# 01072016wearable_v1_3_-_OK.net
KiCad netlist of a schematic drawn in EAGLE
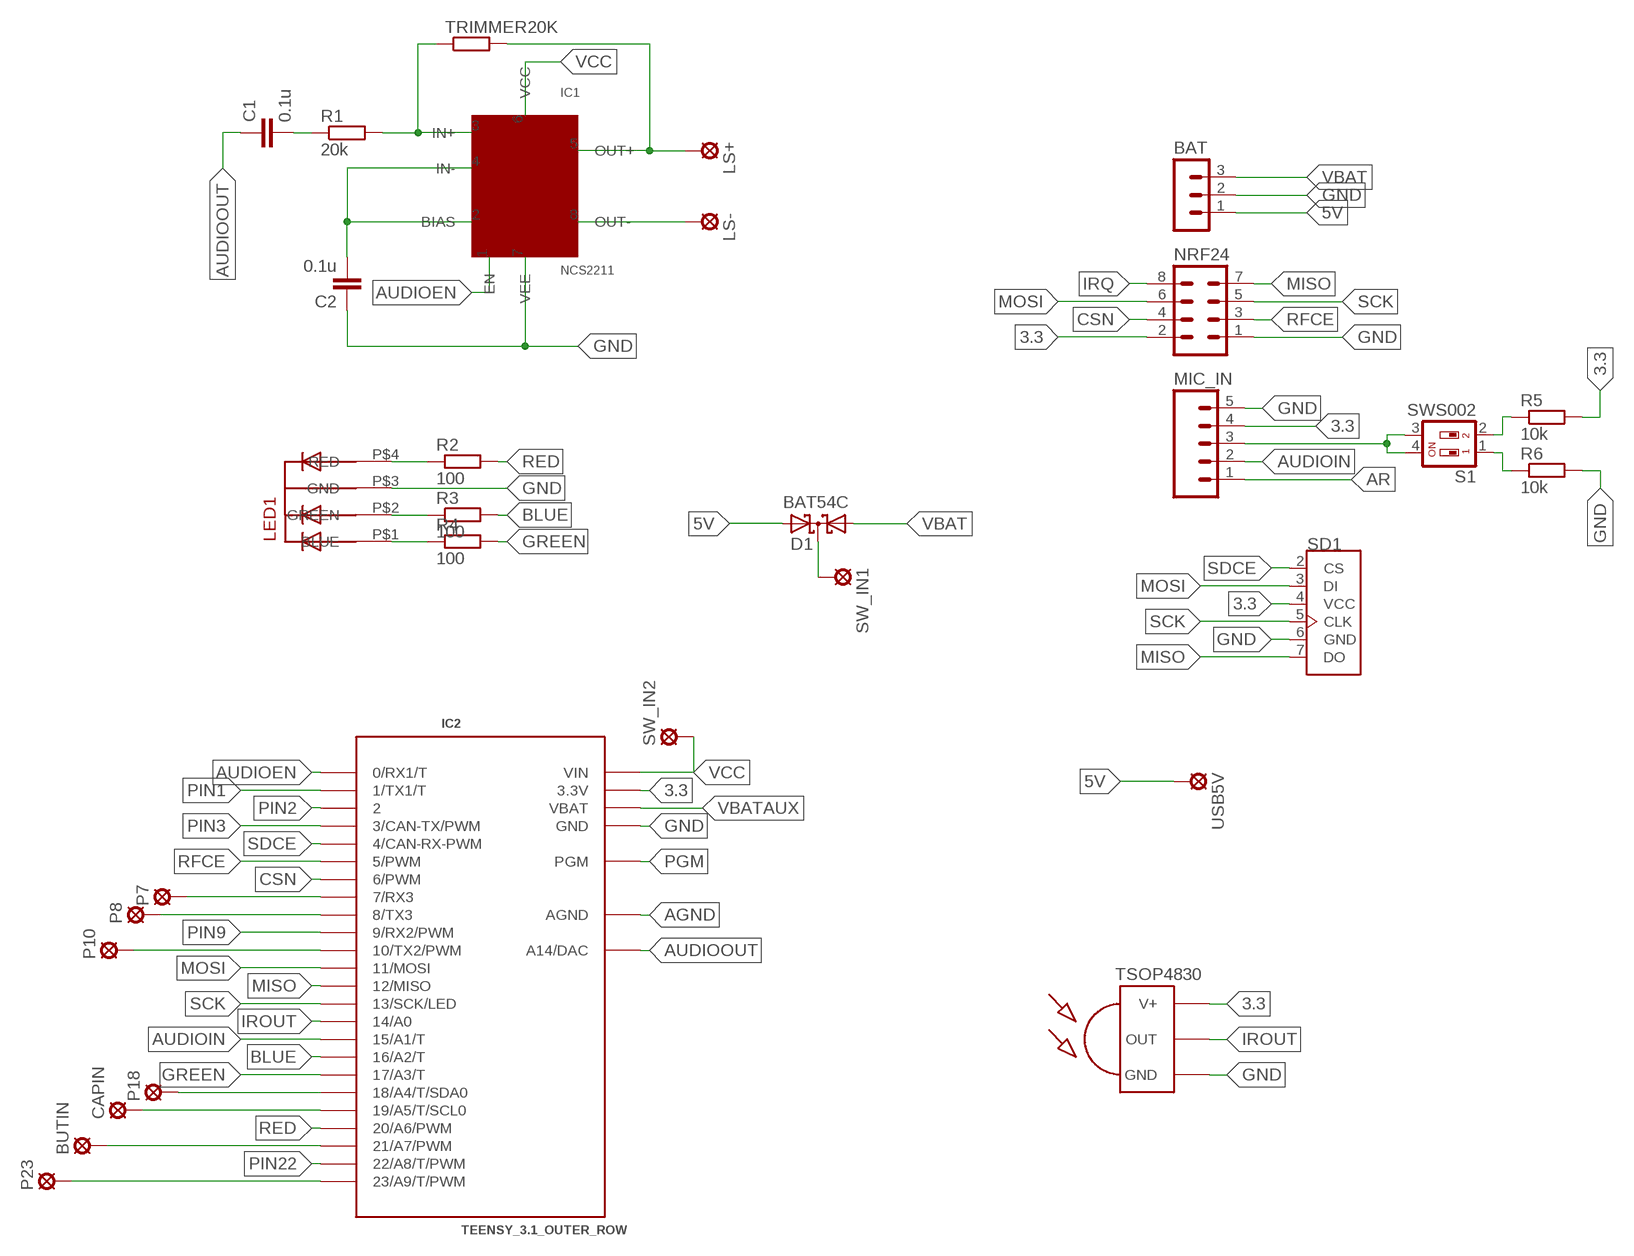
[diagram p0: schematic, sheet 1]

(export (version "E")
  (design (tool "Eeschema 10.0.6"))
  (components
    (comp (ref "BAT")
      (value "MA03-1")
      (footprint "eagle-import:MA03-1")
      (libsource (lib "eagle-import") (part "MA03-1"))
    )
    (comp (ref "BUTIN")
      (value "LSP10")
      (footprint "eagle-import:LSP10")
      (libsource (lib "eagle-import") (part "LSP10"))
    )
    (comp (ref "C1")
      (value "0.1u")
      (footprint "eagle-import:C2.5-2")
      (libsource (lib "eagle-import") (part "C2.5/2"))
    )
    (comp (ref "C2")
      (value "0.1u")
      (footprint "eagle-import:C2.5-2")
      (libsource (lib "eagle-import") (part "C2.5/2"))
    )
    (comp (ref "CAPIN")
      (value "LSP10")
      (footprint "eagle-import:LSP10")
      (libsource (lib "eagle-import") (part "LSP10"))
    )
    (comp (ref "D1")
      (value "BAT54C")
      (footprint "eagle-import:SOT23")
      (libsource (lib "eagle-import") (part "BAT54C"))
    )
    (comp (ref "IC1")
      (value "NCS2211")
      (footprint "eagle-import:SOIC-8")
      (libsource (lib "eagle-import") (part "NCS2211"))
    )
    (comp (ref "IC2")
      (value "TEENSY_3.1_OUTER_ROW")
      (footprint "eagle-import:TEENSY3-OUTER_ROW")
      (libsource (lib "eagle-import") (part "TEENSY_3.1_OUTER_ROW"))
    )
    (comp (ref "LED1")
      (value "5MMRGBLED")
      (footprint "eagle-import:LED5MMRGB")
      (libsource (lib "eagle-import") (part "5MMRGBLED"))
    )
    (comp (ref "LS+")
      (value "LSP10")
      (footprint "eagle-import:LSP10")
      (libsource (lib "eagle-import") (part "LSP10"))
    )
    (comp (ref "LS-")
      (value "LSP10")
      (footprint "eagle-import:LSP10")
      (libsource (lib "eagle-import") (part "LSP10"))
    )
    (comp (ref "MIC_IN")
      (value "MA05")
      (footprint "eagle-import:05PA")
      (libsource (lib "eagle-import") (part "MA05"))
    )
    (comp (ref "NRF24")
      (value "MA04-2")
      (footprint "eagle-import:MA04-2")
      (libsource (lib "eagle-import") (part "MA04-2"))
    )
    (comp (ref "P7")
      (value "LSP10")
      (footprint "eagle-import:LSP10")
      (libsource (lib "eagle-import") (part "LSP10"))
    )
    (comp (ref "P8")
      (value "LSP10")
      (footprint "eagle-import:LSP10")
      (libsource (lib "eagle-import") (part "LSP10"))
    )
    (comp (ref "P10")
      (value "LSP10")
      (footprint "eagle-import:LSP10")
      (libsource (lib "eagle-import") (part "LSP10"))
    )
    (comp (ref "P18")
      (value "LSP10")
      (footprint "eagle-import:LSP10")
      (libsource (lib "eagle-import") (part "LSP10"))
    )
    (comp (ref "P23")
      (value "LSP10")
      (footprint "eagle-import:LSP10")
      (libsource (lib "eagle-import") (part "LSP10"))
    )
    (comp (ref "R1")
      (value "20k")
      (footprint "eagle-import:0204_7")
      (libsource (lib "eagle-import") (part "R-EU_0204/7"))
    )
    (comp (ref "R2")
      (value "100")
      (footprint "eagle-import:0207_2V")
      (libsource (lib "eagle-import") (part "R-EU_0207/2V"))
    )
    (comp (ref "R3")
      (value "100")
      (footprint "eagle-import:0207_2V")
      (libsource (lib "eagle-import") (part "R-EU_0207/2V"))
    )
    (comp (ref "R4")
      (value "100")
      (footprint "eagle-import:0207_2V")
      (libsource (lib "eagle-import") (part "R-EU_0207/2V"))
    )
    (comp (ref "R5")
      (value "10k")
      (footprint "eagle-import:0207_2V")
      (libsource (lib "eagle-import") (part "R-EU_0207/2V"))
    )
    (comp (ref "R6")
      (value "10k")
      (footprint "eagle-import:0207_2V")
      (libsource (lib "eagle-import") (part "R-EU_0207/2V"))
    )
    (comp (ref "S1")
      (value "SWS002")
      (footprint "eagle-import:SMS-002")
      (libsource (lib "eagle-import") (part "SWS002"))
    )
    (comp (ref "SD1")
      (value "MICROSD_SF-MICROSD")
      (footprint "eagle-import:MICROSD_MICROSD")
      (libsource (lib "eagle-import") (part "MICROSD_SF-MICROSD"))
    )
    (comp (ref "SW_IN1")
      (value "SE11")
      (footprint "eagle-import:SE11")
      (libsource (lib "eagle-import") (part "SE11"))
    )
    (comp (ref "SW_IN2")
      (value "SE11")
      (footprint "eagle-import:SE11")
      (libsource (lib "eagle-import") (part "SE11"))
    )
    (comp (ref "TRIMMER20K")
      (value "R-EU_0207/2V")
      (footprint "eagle-import:0207_2V")
      (libsource (lib "eagle-import") (part "R-EU_0207/2V"))
    )
    (comp (ref "U$1")
      (value "TSOP4830")
      (footprint "eagle-import:TSOP18XX")
      (libsource (lib "eagle-import") (part "TSOP4830"))
    )
    (comp (ref "USB5V")
      (value "LSP10")
      (footprint "eagle-import:LSP10")
      (libsource (lib "eagle-import") (part "LSP10"))
    )
  )
  (nets
    (net (code "1") (name "3.3") (class "Default")
      (node (ref "IC2") (pin "3.3V") (pinfunction "3.3V_3.3V") (pintype "power_in"))
      (node (ref "IC2") (pin "3.3V1") (pinfunction "3.3V_3.3V1") (pintype "power_in"))
      (node (ref "MIC_IN") (pin "4") (pinfunction "4_4") (pintype "passive"))
      (node (ref "NRF24") (pin "2") (pinfunction "2_2") (pintype "passive"))
      (node (ref "R5") (pin "2") (pinfunction "2_2") (pintype "passive"))
      (node (ref "SD1") (pin "4") (pinfunction "VCC_4") (pintype "power_in"))
      (node (ref "U$1") (pin "VCC") (pinfunction "V+_VCC") (pintype "bidirectional"))
    )
    (net (code "2") (name "5V") (class "Default")
      (node (ref "BAT") (pin "1") (pinfunction "1_1") (pintype "passive"))
      (node (ref "D1") (pin "2") (pinfunction "A2_2") (pintype "passive"))
      (node (ref "USB5V") (pin "MP") (pinfunction "MP_MP") (pintype "passive"))
    )
    (net (code "3") (name "AGND") (class "Default")
      (node (ref "IC2") (pin "AGND") (pinfunction "AGND_AGND") (pintype "power_in"))
    )
    (net (code "4") (name "AR") (class "Default")
      (node (ref "MIC_IN") (pin "1") (pinfunction "1_1") (pintype "passive"))
    )
    (net (code "5") (name "AUDIOEN") (class "Default")
      (node (ref "IC1") (pin "1") (pinfunction "EN_1") (pintype "bidirectional"))
      (node (ref "IC2") (pin "0") (pinfunction "0/RX1/T_0") (pintype "bidirectional"))
    )
    (net (code "6") (name "AUDIOIN") (class "Default")
      (node (ref "IC2") (pin "15/A1") (pinfunction "15/A1/T_15/A1") (pintype "bidirectional"))
      (node (ref "MIC_IN") (pin "2") (pinfunction "2_2") (pintype "passive"))
    )
    (net (code "7") (name "AUDIOOUT") (class "Default")
      (node (ref "C1") (pin "1") (pinfunction "1_1") (pintype "passive"))
      (node (ref "IC2") (pin "RESET/DAC") (pinfunction "A14/DAC_RESET/DAC") (pintype "bidirectional"))
    )
    (net (code "8") (name "BLUE") (class "Default")
      (node (ref "IC2") (pin "16/A2") (pinfunction "16/A2/T_16/A2") (pintype "bidirectional"))
      (node (ref "R3") (pin "2") (pinfunction "2_2") (pintype "passive"))
    )
    (net (code "9") (name "CSN") (class "Default")
      (node (ref "IC2") (pin "6") (pinfunction "6/PWM_6") (pintype "bidirectional"))
      (node (ref "NRF24") (pin "4") (pinfunction "4_4") (pintype "passive"))
    )
    (net (code "10") (name "GND") (class "Default")
      (node (ref "BAT") (pin "2") (pinfunction "2_2") (pintype "passive"))
      (node (ref "C2") (pin "1") (pinfunction "1_1") (pintype "passive"))
      (node (ref "IC1") (pin "7") (pinfunction "VEE_7") (pintype "bidirectional"))
      (node (ref "IC2") (pin "GND") (pinfunction "GND_GND") (pintype "power_in"))
      (node (ref "IC2") (pin "GND1") (pinfunction "GND_GND1") (pintype "power_in"))
      (node (ref "LED1") (pin "P$3") (pinfunction "GND_P$3") (pintype "bidirectional"))
      (node (ref "MIC_IN") (pin "5") (pinfunction "5_5") (pintype "passive"))
      (node (ref "NRF24") (pin "1") (pinfunction "1_1") (pintype "passive"))
      (node (ref "R6") (pin "2") (pinfunction "2_2") (pintype "passive"))
      (node (ref "SD1") (pin "6") (pinfunction "GND_6") (pintype "power_in"))
      (node (ref "U$1") (pin "GND") (pinfunction "GND_GND") (pintype "bidirectional"))
    )
    (net (code "11") (name "GREEN") (class "Default")
      (node (ref "IC2") (pin "17/A3") (pinfunction "17/A3/T_17/A3") (pintype "bidirectional"))
      (node (ref "R4") (pin "2") (pinfunction "2_2") (pintype "passive"))
    )
    (net (code "12") (name "IROUT") (class "Default")
      (node (ref "IC2") (pin "14/A0") (pinfunction "14/A0_14/A0") (pintype "bidirectional"))
      (node (ref "U$1") (pin "OUT") (pinfunction "OUT_OUT") (pintype "bidirectional"))
    )
    (net (code "13") (name "IRQ") (class "Default")
      (node (ref "NRF24") (pin "8") (pinfunction "8_8") (pintype "passive"))
    )
    (net (code "14") (name "MISO") (class "Default")
      (node (ref "IC2") (pin "12") (pinfunction "12/MISO_12") (pintype "bidirectional"))
      (node (ref "NRF24") (pin "7") (pinfunction "7_7") (pintype "passive"))
      (node (ref "SD1") (pin "7") (pinfunction "DO_7") (pintype "output"))
    )
    (net (code "15") (name "MOSI") (class "Default")
      (node (ref "IC2") (pin "11") (pinfunction "11/MOSI_11") (pintype "bidirectional"))
      (node (ref "NRF24") (pin "6") (pinfunction "6_6") (pintype "passive"))
      (node (ref "SD1") (pin "3") (pinfunction "DI_3") (pintype "input"))
    )
    (net (code "16") (name "Net-(C1-Pad2)") (class "Default")
      (node (ref "C1") (pin "2") (pinfunction "2_2") (pintype "passive"))
      (node (ref "R1") (pin "1") (pinfunction "1_1") (pintype "passive"))
    )
    (net (code "17") (name "Net-(D1-CC)") (class "Default")
      (node (ref "D1") (pin "3") (pinfunction "CC_3") (pintype "passive"))
      (node (ref "SW_IN1") (pin "MP") (pinfunction "MP_MP") (pintype "passive"))
    )
    (net (code "18") (name "Net-(IC1-BIAS)") (class "Default")
      (node (ref "C2") (pin "2") (pinfunction "2_2") (pintype "passive"))
      (node (ref "IC1") (pin "2") (pinfunction "BIAS_2") (pintype "bidirectional"))
      (node (ref "IC1") (pin "4") (pinfunction "IN-_4") (pintype "bidirectional"))
    )
    (net (code "19") (name "Net-(IC1-IN+)") (class "Default")
      (node (ref "IC1") (pin "3") (pinfunction "IN+_3") (pintype "bidirectional"))
      (node (ref "R1") (pin "2") (pinfunction "2_2") (pintype "passive"))
      (node (ref "TRIMMER20K") (pin "1") (pinfunction "1_1") (pintype "passive"))
    )
    (net (code "20") (name "Net-(IC1-OUT+)") (class "Default")
      (node (ref "IC1") (pin "5") (pinfunction "OUT+_5") (pintype "bidirectional"))
      (node (ref "LS+") (pin "MP") (pinfunction "MP_MP") (pintype "passive"))
      (node (ref "TRIMMER20K") (pin "2") (pinfunction "2_2") (pintype "passive"))
    )
    (net (code "21") (name "Net-(IC1-OUT-)") (class "Default")
      (node (ref "IC1") (pin "8") (pinfunction "OUT-_8") (pintype "bidirectional"))
      (node (ref "LS-") (pin "MP") (pinfunction "MP_MP") (pintype "passive"))
    )
    (net (code "22") (name "Net-(IC2-7{slash}RX3)") (class "Default")
      (node (ref "IC2") (pin "7") (pinfunction "7/RX3_7") (pintype "bidirectional"))
      (node (ref "P7") (pin "MP") (pinfunction "MP_MP") (pintype "passive"))
    )
    (net (code "23") (name "Net-(IC2-8{slash}TX3)") (class "Default")
      (node (ref "IC2") (pin "8") (pinfunction "8/TX3_8") (pintype "bidirectional"))
      (node (ref "P8") (pin "MP") (pinfunction "MP_MP") (pintype "passive"))
    )
    (net (code "24") (name "Net-(IC2-10{slash}TX2{slash}PWM)") (class "Default")
      (node (ref "IC2") (pin "10") (pinfunction "10/TX2/PWM_10") (pintype "bidirectional"))
      (node (ref "P10") (pin "MP") (pinfunction "MP_MP") (pintype "passive"))
    )
    (net (code "25") (name "Net-(IC2-18{slash}A4{slash}T{slash}SDA0)") (class "Default")
      (node (ref "IC2") (pin "18/A4") (pinfunction "18/A4/T/SDA0_18/A4") (pintype "bidirectional"))
      (node (ref "P18") (pin "MP") (pinfunction "MP_MP") (pintype "passive"))
    )
    (net (code "26") (name "Net-(IC2-19{slash}A5{slash}T{slash}SCL0)") (class "Default")
      (node (ref "CAPIN") (pin "MP") (pinfunction "MP_MP") (pintype "passive"))
      (node (ref "IC2") (pin "19/A5") (pinfunction "19/A5/T/SCL0_19/A5") (pintype "bidirectional"))
    )
    (net (code "27") (name "Net-(IC2-21{slash}A7{slash}PWM)") (class "Default")
      (node (ref "BUTIN") (pin "MP") (pinfunction "MP_MP") (pintype "passive"))
      (node (ref "IC2") (pin "21/A7") (pinfunction "21/A7/PWM_21/A7") (pintype "bidirectional"))
    )
    (net (code "28") (name "Net-(IC2-23{slash}A9{slash}T{slash}PWM)") (class "Default")
      (node (ref "IC2") (pin "23/A9") (pinfunction "23/A9/T/PWM_23/A9") (pintype "bidirectional"))
      (node (ref "P23") (pin "MP") (pinfunction "MP_MP") (pintype "passive"))
    )
    (net (code "29") (name "Net-(LED1-BLUE)") (class "Default")
      (node (ref "LED1") (pin "P$1") (pinfunction "BLUE_P$1") (pintype "bidirectional"))
      (node (ref "R4") (pin "1") (pinfunction "1_1") (pintype "passive"))
    )
    (net (code "30") (name "Net-(LED1-GREEN)") (class "Default")
      (node (ref "LED1") (pin "P$2") (pinfunction "GREEN_P$2") (pintype "bidirectional"))
      (node (ref "R3") (pin "1") (pinfunction "1_1") (pintype "passive"))
    )
    (net (code "31") (name "Net-(LED1-RED)") (class "Default")
      (node (ref "LED1") (pin "P$4") (pinfunction "RED_P$4") (pintype "bidirectional"))
      (node (ref "R2") (pin "1") (pinfunction "1_1") (pintype "passive"))
    )
    (net (code "32") (name "Net-(MIC_IN-Pad3)") (class "Default")
      (node (ref "MIC_IN") (pin "3") (pinfunction "3_3") (pintype "passive"))
      (node (ref "S1") (pin "3") (pinfunction "3_3") (pintype "passive"))
      (node (ref "S1") (pin "4") (pinfunction "4_4") (pintype "passive"))
    )
    (net (code "33") (name "Net-(R5-Pad1)") (class "Default")
      (node (ref "R5") (pin "1") (pinfunction "1_1") (pintype "passive"))
      (node (ref "S1") (pin "2") (pinfunction "2_2") (pintype "passive"))
    )
    (net (code "34") (name "Net-(R6-Pad1)") (class "Default")
      (node (ref "R6") (pin "1") (pinfunction "1_1") (pintype "passive"))
      (node (ref "S1") (pin "1") (pinfunction "1_1") (pintype "passive"))
    )
    (net (code "35") (name "PGM") (class "Default")
      (node (ref "IC2") (pin "PGM") (pinfunction "PGM_PGM") (pintype "bidirectional"))
    )
    (net (code "36") (name "PIN1") (class "Default")
      (node (ref "IC2") (pin "1") (pinfunction "1/TX1/T_1") (pintype "bidirectional"))
    )
    (net (code "37") (name "PIN2") (class "Default")
      (node (ref "IC2") (pin "2") (pinfunction "2_2") (pintype "bidirectional"))
    )
    (net (code "38") (name "PIN3") (class "Default")
      (node (ref "IC2") (pin "3") (pinfunction "3/CAN-TX/PWM_3") (pintype "bidirectional"))
    )
    (net (code "39") (name "PIN9") (class "Default")
      (node (ref "IC2") (pin "9") (pinfunction "9/RX2/PWM_9") (pintype "bidirectional"))
    )
    (net (code "40") (name "PIN22") (class "Default")
      (node (ref "IC2") (pin "22/A8") (pinfunction "22/A8/T/PWM_22/A8") (pintype "bidirectional"))
    )
    (net (code "41") (name "RED") (class "Default")
      (node (ref "IC2") (pin "20/A6") (pinfunction "20/A6/PWM_20/A6") (pintype "bidirectional"))
      (node (ref "R2") (pin "2") (pinfunction "2_2") (pintype "passive"))
    )
    (net (code "42") (name "RFCE") (class "Default")
      (node (ref "IC2") (pin "5") (pinfunction "5/PWM_5") (pintype "bidirectional"))
      (node (ref "NRF24") (pin "3") (pinfunction "3_3") (pintype "passive"))
    )
    (net (code "43") (name "SCK") (class "Default")
      (node (ref "IC2") (pin "13") (pinfunction "13/SCK/LED_13") (pintype "bidirectional"))
      (node (ref "NRF24") (pin "5") (pinfunction "5_5") (pintype "passive"))
      (node (ref "SD1") (pin "5") (pinfunction "CLK_5") (pintype "input"))
    )
    (net (code "44") (name "SDCE") (class "Default")
      (node (ref "IC2") (pin "4") (pinfunction "4/CAN-RX-PWM_4") (pintype "bidirectional"))
      (node (ref "SD1") (pin "2") (pinfunction "CS_2") (pintype "input"))
    )
    (net (code "45") (name "VBAT") (class "Default")
      (node (ref "BAT") (pin "3") (pinfunction "3_3") (pintype "passive"))
      (node (ref "D1") (pin "1") (pinfunction "A1_1") (pintype "passive"))
    )
    (net (code "46") (name "VBATAUX") (class "Default")
      (node (ref "IC2") (pin "VBAT") (pinfunction "VBAT_VBAT") (pintype "power_in"))
    )
    (net (code "47") (name "VCC") (class "Default")
      (node (ref "IC1") (pin "6") (pinfunction "VCC_6") (pintype "bidirectional"))
      (node (ref "IC2") (pin "VIN") (pinfunction "VIN_VIN") (pintype "power_in"))
      (node (ref "SW_IN2") (pin "MP") (pinfunction "MP_MP") (pintype "passive"))
    )
  )
)
